# AuxHalfH.net
KiCad netlist of a schematic drawn in Altium Designer
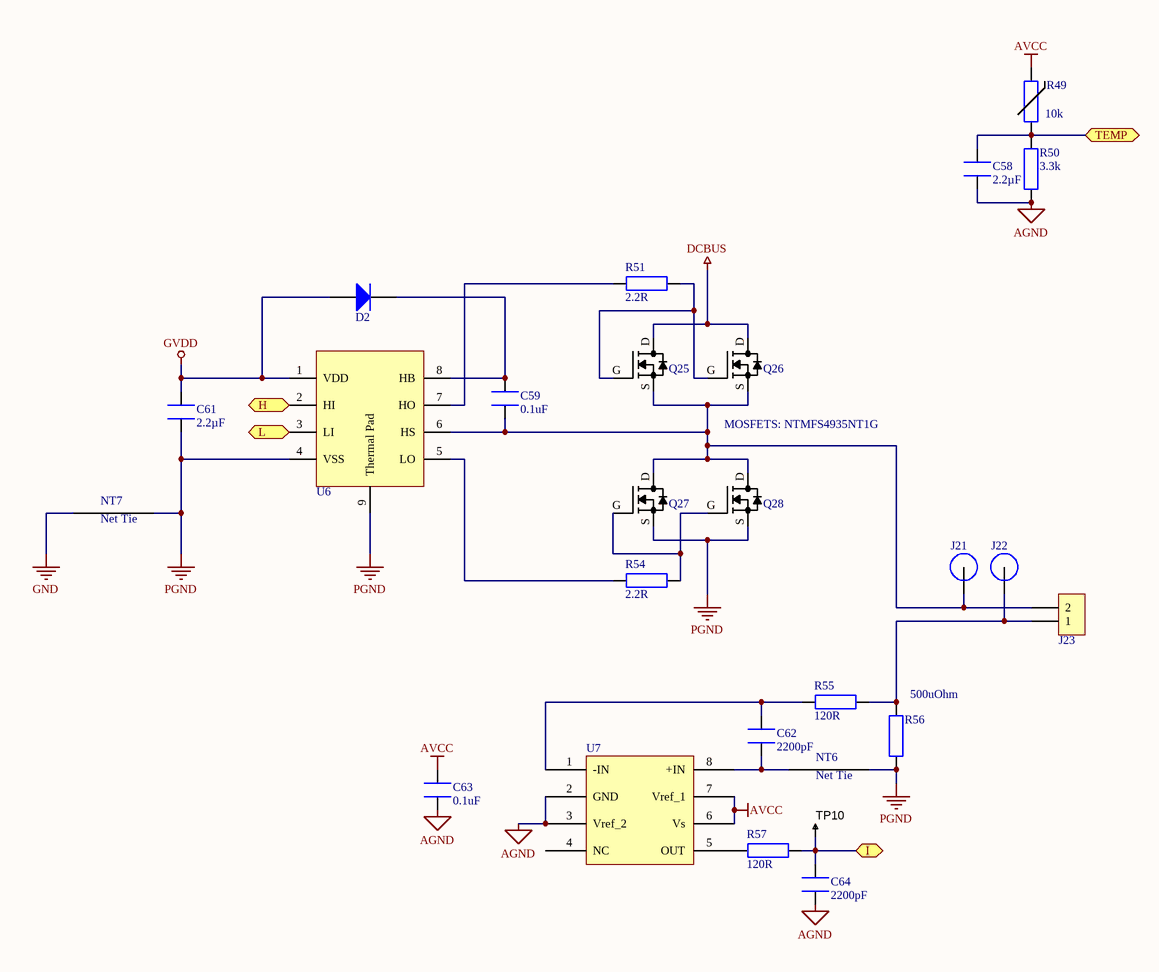
[diagram p0: AuxHalfH.SchDoc]

(export (version "E")
  (design (tool "Eeschema 10.0.6"))
  (components
    (comp (ref "C58")
      (value "2.2µF")
      (footprint "CAPC1608X09L")
      (description "CAP CER 2.2UF 16V X5R 0603")
      (fields
        (field (name "MANUFACTURER") "Murata Electronics North America")
        (field (name "MANUFACTURER PART NUMBER") "GRM188R61C225KE15D")
      )
      (libsource (lib "CustomComponents") (part "GRM188R61C225KE15D"))
    )
    (comp (ref "C59")
      (value "0.1uF")
      (footprint "CAPC1608X09L")
      (description "CAP CER 0.1UF 50V X7R 0603")
      (fields
        (field (name "MANUFACTURER") "Murata Electronics North America")
        (field (name "MANUFACTURER PART NUMBER") "GRM188R71H104KA93D")
      )
      (libsource (lib "CustomComponents") (part "GRM188R71H104KA93D"))
    )
    (comp (ref "C61")
      (value "2.2µF")
      (footprint "CAPC1608X09L")
      (description "CAP CER 2.2UF 16V X5R 0603")
      (fields
        (field (name "MANUFACTURER") "Murata Electronics North America")
        (field (name "MANUFACTURER PART NUMBER") "GRM188R61C225KE15D")
      )
      (libsource (lib "CustomComponents") (part "GRM188R61C225KE15D"))
    )
    (comp (ref "C62")
      (value "2200pF")
      (footprint "CAPC1608X09L")
      (description "CAP CER 2200PF 50V NP0 0603")
      (fields
        (field (name "MANUFACTURER") "Murata Electronics North America")
        (field (name "TOLERANCE") "±5%")
      )
      (libsource (lib "CustomComponents") (part "GRM1885C1H222JA01D"))
    )
    (comp (ref "C63")
      (value "0.1uF")
      (footprint "CAPC1608X09L")
      (description "CAP CER 0.1UF 50V X7R 0603")
      (fields
        (field (name "MANUFACTURER") "Murata Electronics North America")
        (field (name "MANUFACTURER PART NUMBER") "GRM188R71H104KA93D")
      )
      (libsource (lib "CustomComponents") (part "GRM188R71H104KA93D"))
    )
    (comp (ref "C64")
      (value "2200pF")
      (footprint "CAPC1608X09L")
      (description "CAP CER 2200PF 50V NP0 0603")
      (fields
        (field (name "MANUFACTURER") "Murata Electronics North America")
        (field (name "TOLERANCE") "±5%")
      )
      (libsource (lib "CustomComponents") (part "GRM1885C1H222JA01D"))
    )
    (comp (ref "D2")
      (value "~")
      (footprint "DIOM2717X10N")
      (description "Rectifier Diode, Single, 40 V, 1 A, SOD-123FL, 2, 550 mV")
      (libsource (lib "CustomComponents") (part "MBR140SFT1G"))
    )
    (comp (ref "J21")
      (value "~")
      (footprint "M3 Spade Hole")
      (description "M3 Spade Terminal")
      (libsource (lib "CustomComponents") (part "M3 Spade Terminal"))
    )
    (comp (ref "J22")
      (value "~")
      (footprint "M3 Spade Hole")
      (description "M3 Spade Terminal")
      (libsource (lib "CustomComponents") (part "M3 Spade Terminal"))
    )
    (comp (ref "J23")
      (value "1868076")
      (footprint "1868076")
      (description "CONN TERM BLOCK 2POS 7.62MM")
      (fields (field (name "MANUFACTURER") "Phoenix Contact") (field (name "VOLTAGE") "300V"))
      (libsource (lib "CustomComponents") (part "1868076"))
    )
    (comp (ref "NT6")
      (value "0.25mm")
      (footprint "NetTie_0.25mm")
      (libsource (lib "CustomComponents") (part "NetTie_0.25mm"))
    )
    (comp (ref "NT7")
      (value "0.25mm")
      (footprint "NetTie_0.25mm")
      (libsource (lib "CustomComponents") (part "NetTie_0.25mm"))
    )
    (comp (ref "Q25")
      (value "FILL_FOOTPRINT")
      (footprint "SO8FL_FILL")
      (description "MOSFET N-CH 30V 13A SO8FL")
      (fields
        (field (name "MANUFACTURER") "ON Semiconductor")
        (field (name "MANUFACTURER PART NUMBER") "NTMFS4935NT1G")
      )
      (libsource (lib "CustomComponents") (part "NTMFS4935NT1G"))
    )
    (comp (ref "Q26")
      (value "~")
      (footprint "SO8FL")
      (description "MOSFET N-CH 30V 13A SO8FL")
      (fields
        (field (name "MANUFACTURER") "ON Semiconductor")
        (field (name "MANUFACTURER PART NUMBER") "NTMFS4935NT1G")
      )
      (libsource (lib "CustomComponents") (part "NTMFS4935NT1G"))
    )
    (comp (ref "Q27")
      (value "~")
      (footprint "SO8FL")
      (description "MOSFET N-CH 30V 13A SO8FL")
      (fields
        (field (name "MANUFACTURER") "ON Semiconductor")
        (field (name "MANUFACTURER PART NUMBER") "NTMFS4935NT1G")
      )
      (libsource (lib "CustomComponents") (part "NTMFS4935NT1G"))
    )
    (comp (ref "Q28")
      (value "~")
      (footprint "SO8FL")
      (description "MOSFET N-CH 30V 13A SO8FL")
      (fields
        (field (name "MANUFACTURER") "ON Semiconductor")
        (field (name "MANUFACTURER PART NUMBER") "NTMFS4935NT1G")
      )
      (libsource (lib "CustomComponents") (part "NTMFS4935NT1G"))
    )
    (comp (ref "R49")
      (value "10k")
      (footprint "RESC1005X40N")
      (description "THERMISTOR 10K OHM NTC 0402 SMD")
      (libsource (lib "CustomComponents") (part "NCP15XH103F03RC"))
    )
    (comp (ref "R50")
      (value "3.3k")
      (footprint "RESC1608X55N")
      (description "RES SMD 3.3K OHM 1% 1/10W 0603")
      (fields
        (field (name "MANUFACTURER") "Yageo")
        (field (name "MANUFACTURER PART NUMBER") "RC0603FR-073K3L")
      )
      (libsource (lib "CustomComponents") (part "RC0603FR-073K3L"))
    )
    (comp (ref "R51")
      (value "2.2R")
      (footprint "RESC1608X55N")
      (description "RES SMD 2.2 OHM 1% 1/10W 0603")
      (fields
        (field (name "MANUFACTURER") "Yageo")
        (field (name "MANUFACTURER PART NUMBER") "RC0603FR-072R2L")
      )
      (libsource (lib "CustomComponents") (part "RC0603FR-072R2L"))
    )
    (comp (ref "R54")
      (value "2.2R")
      (footprint "RESC1608X55N")
      (description "RES SMD 2.2 OHM 1% 1/10W 0603")
      (fields
        (field (name "MANUFACTURER") "Yageo")
        (field (name "MANUFACTURER PART NUMBER") "RC0603FR-072R2L")
      )
      (libsource (lib "CustomComponents") (part "RC0603FR-072R2L"))
    )
    (comp (ref "R55")
      (value "120R")
      (footprint "RESC1608X55N")
      (description "RES SMD 120 OHM 1% 1/10W 0603")
      (fields
        (field (name "MANUFACTURER") "Yageo")
        (field (name "MANUFACTURER PART NUMBER") "RC0603FR-07120RL")
      )
      (libsource (lib "CustomComponents") (part "RC0603FR-07120RL"))
    )
    (comp (ref "R56")
      (value "500uOhm")
      (footprint "RESC6432X09N")
      (description "RES SMD 0.0005 OHM 1% 3W 2512")
      (fields (field (name "MANUFACTURER") "Riedon") (field (name "TOLERANCE") "±1%"))
      (libsource (lib "CustomComponents") (part "CSR2512C0R0005F"))
    )
    (comp (ref "R57")
      (value "120R")
      (footprint "RESC1608X06L")
      (description "RES SMD 120 OHM 1% 1/10W 0603")
      (fields
        (field (name "MANUFACTURER") "Yageo")
        (field (name "MANUFACTURER PART NUMBER") "RC0603FR-07120RL")
      )
      (libsource (lib "CustomComponents") (part "RC0603FR-07120RL"))
    )
    (comp (ref "TP10")
      (value "TESTPOINT")
      (footprint "TP-R30")
      (description "SMD test pin")
      (libsource (lib "PBL - Test Points") (part "TESTPOINT"))
    )
    (comp (ref "U6")
      (value "~")
      (footprint "SON80P400X80_HS-9N")
      (description "DRIVER, MOSFET, HALF BRIDGE, WSON-8, 1A")
      (libsource (lib "CustomComponents") (part "LM5109BSD/NOPB"))
    )
    (comp (ref "U7")
      (value "~")
      (footprint "SOIC127P600X175-8N")
      (description "ANALOG DEVICES Current Sense Amplifier, Bidirectional, 1, 130 µA, NSOIC")
      (libsource (lib "CustomComponents") (part "AD8418WBRZ"))
    )
  )
  (nets
    (net (code "1") (name "/H") (class "Default")
      (node (ref "U6") (pin "2") (pinfunction "HI_2") (pintype "passive"))
    )
    (net (code "2") (name "/I") (class "Default")
      (node (ref "C64") (pin "1") (pinfunction "1_1") (pintype "passive"))
      (node (ref "R57") (pin "2") (pinfunction "0_2") (pintype "passive"))
      (node (ref "TP10") (pin "1") (pintype "passive"))
    )
    (net (code "3") (name "/L") (class "Default")
      (node (ref "U6") (pin "3") (pinfunction "LI_3") (pintype "passive"))
    )
    (net (code "4") (name "/TEMP") (class "Default")
      (node (ref "C58") (pin "2") (pinfunction "2_2") (pintype "passive"))
      (node (ref "R49") (pin "1") (pinfunction "0_1") (pintype "passive"))
      (node (ref "R50") (pin "1") (pinfunction "0_1") (pintype "passive"))
    )
    (net (code "5") (name "AGND") (class "Default")
      (node (ref "C58") (pin "1") (pinfunction "1_1") (pintype "passive"))
      (node (ref "C63") (pin "2") (pinfunction "2_2") (pintype "passive"))
      (node (ref "C64") (pin "2") (pinfunction "2_2") (pintype "passive"))
      (node (ref "R50") (pin "2") (pinfunction "0_2") (pintype "passive"))
      (node (ref "U7") (pin "2") (pinfunction "GND_2") (pintype "passive"))
      (node (ref "U7") (pin "3") (pinfunction "Vref_2_3") (pintype "passive"))
    )
    (net (code "6") (name "AVCC") (class "Default")
      (node (ref "C63") (pin "1") (pinfunction "1_1") (pintype "passive"))
      (node (ref "R49") (pin "2") (pinfunction "0_2") (pintype "passive"))
      (node (ref "U7") (pin "6") (pinfunction "Vs_6") (pintype "passive"))
      (node (ref "U7") (pin "7") (pinfunction "Vref_1_7") (pintype "passive"))
    )
    (net (code "7") (name "DCBUS") (class "Default")
      (node (ref "Q25") (pin "D") (pinfunction "D_D") (pintype "passive"))
      (node (ref "Q26") (pin "D") (pinfunction "D_D") (pintype "passive"))
    )
    (net (code "8") (name "GND") (class "Default") (node (ref "NT7") (pin "1") (pintype "passive")))
    (net (code "9") (name "GVDD") (class "Default")
      (node (ref "C61") (pin "2") (pinfunction "2_2") (pintype "passive"))
      (node (ref "D2") (pin "A") (pinfunction "A_A") (pintype "passive"))
      (node (ref "U6") (pin "1") (pinfunction "VDD_1") (pintype "passive"))
    )
    (net (code "10") (name "Net-(J22-Pad1)") (class "Default")
      (node (ref "J22") (pin "1") (pinfunction "1_1") (pintype "passive"))
      (node (ref "J23") (pin "1") (pinfunction "1_1") (pintype "passive"))
      (node (ref "R55") (pin "2") (pinfunction "0_2") (pintype "passive"))
      (node (ref "R56") (pin "1") (pinfunction "0_1") (pintype "passive"))
    )
    (net (code "11") (name "Net-(Q25-PadG)") (class "Default")
      (node (ref "Q25") (pin "G") (pinfunction "G_G") (pintype "passive"))
      (node (ref "Q26") (pin "G") (pinfunction "G_G") (pintype "passive"))
      (node (ref "R51") (pin "2") (pinfunction "0_2") (pintype "passive"))
    )
    (net (code "12") (name "Net-(Q27-PadG)") (class "Default")
      (node (ref "Q27") (pin "G") (pinfunction "G_G") (pintype "passive"))
      (node (ref "Q28") (pin "G") (pinfunction "G_G") (pintype "passive"))
      (node (ref "R54") (pin "2") (pinfunction "0_2") (pintype "passive"))
    )
    (net (code "13") (name "Net-(U6-HB)") (class "Default")
      (node (ref "C59") (pin "1") (pinfunction "1_1") (pintype "passive"))
      (node (ref "D2") (pin "K") (pinfunction "K_K") (pintype "passive"))
      (node (ref "U6") (pin "8") (pinfunction "HB_8") (pintype "passive"))
    )
    (net (code "14") (name "Net-(U6-HO)") (class "Default")
      (node (ref "R51") (pin "1") (pinfunction "0_1") (pintype "passive"))
      (node (ref "U6") (pin "7") (pinfunction "HO_7") (pintype "passive"))
    )
    (net (code "15") (name "Net-(U6-HS)") (class "Default")
      (node (ref "C59") (pin "2") (pinfunction "2_2") (pintype "passive"))
      (node (ref "J21") (pin "1") (pinfunction "1_1") (pintype "passive"))
      (node (ref "J23") (pin "2") (pinfunction "2_2") (pintype "passive"))
      (node (ref "Q25") (pin "S") (pinfunction "S_S") (pintype "passive"))
      (node (ref "Q26") (pin "S") (pinfunction "S_S") (pintype "passive"))
      (node (ref "Q27") (pin "D") (pinfunction "D_D") (pintype "passive"))
      (node (ref "Q28") (pin "D") (pinfunction "D_D") (pintype "passive"))
      (node (ref "U6") (pin "6") (pinfunction "HS_6") (pintype "passive"))
    )
    (net (code "16") (name "Net-(U6-LO)") (class "Default")
      (node (ref "R54") (pin "1") (pinfunction "0_1") (pintype "passive"))
      (node (ref "U6") (pin "5") (pinfunction "LO_5") (pintype "passive"))
    )
    (net (code "17") (name "Net-(U7-+IN)") (class "Default")
      (node (ref "C62") (pin "2") (pinfunction "2_2") (pintype "passive"))
      (node (ref "NT6") (pin "1") (pintype "passive"))
      (node (ref "U7") (pin "8") (pinfunction "+IN_8") (pintype "passive"))
    )
    (net (code "18") (name "Net-(U7--IN)") (class "Default")
      (node (ref "C62") (pin "1") (pinfunction "1_1") (pintype "passive"))
      (node (ref "R55") (pin "1") (pinfunction "0_1") (pintype "passive"))
      (node (ref "U7") (pin "1") (pinfunction "-IN_1") (pintype "passive"))
    )
    (net (code "19") (name "Net-(U7-OUT)") (class "Default")
      (node (ref "R57") (pin "1") (pinfunction "0_1") (pintype "passive"))
      (node (ref "U7") (pin "5") (pinfunction "OUT_5") (pintype "passive"))
    )
    (net (code "20") (name "PGND") (class "Default")
      (node (ref "C61") (pin "1") (pinfunction "1_1") (pintype "passive"))
      (node (ref "NT6") (pin "2") (pintype "passive"))
      (node (ref "NT7") (pin "2") (pintype "passive"))
      (node (ref "Q27") (pin "S") (pinfunction "S_S") (pintype "passive"))
      (node (ref "Q28") (pin "S") (pinfunction "S_S") (pintype "passive"))
      (node (ref "R56") (pin "2") (pinfunction "0_2") (pintype "passive"))
      (node (ref "U6") (pin "4") (pinfunction "VSS_4") (pintype "passive"))
      (node (ref "U6") (pin "9") (pinfunction "Thermal_Pad_9") (pintype "passive"))
    )
    (net (code "21") (name "unconnected-(U7-NC-Pad4)") (class "Default")
      (node (ref "U7") (pin "4") (pinfunction "NC_4") (pintype "passive"))
    )
  )
)
